# Connector.net
KiCad netlist of a schematic drawn in Altium Designer
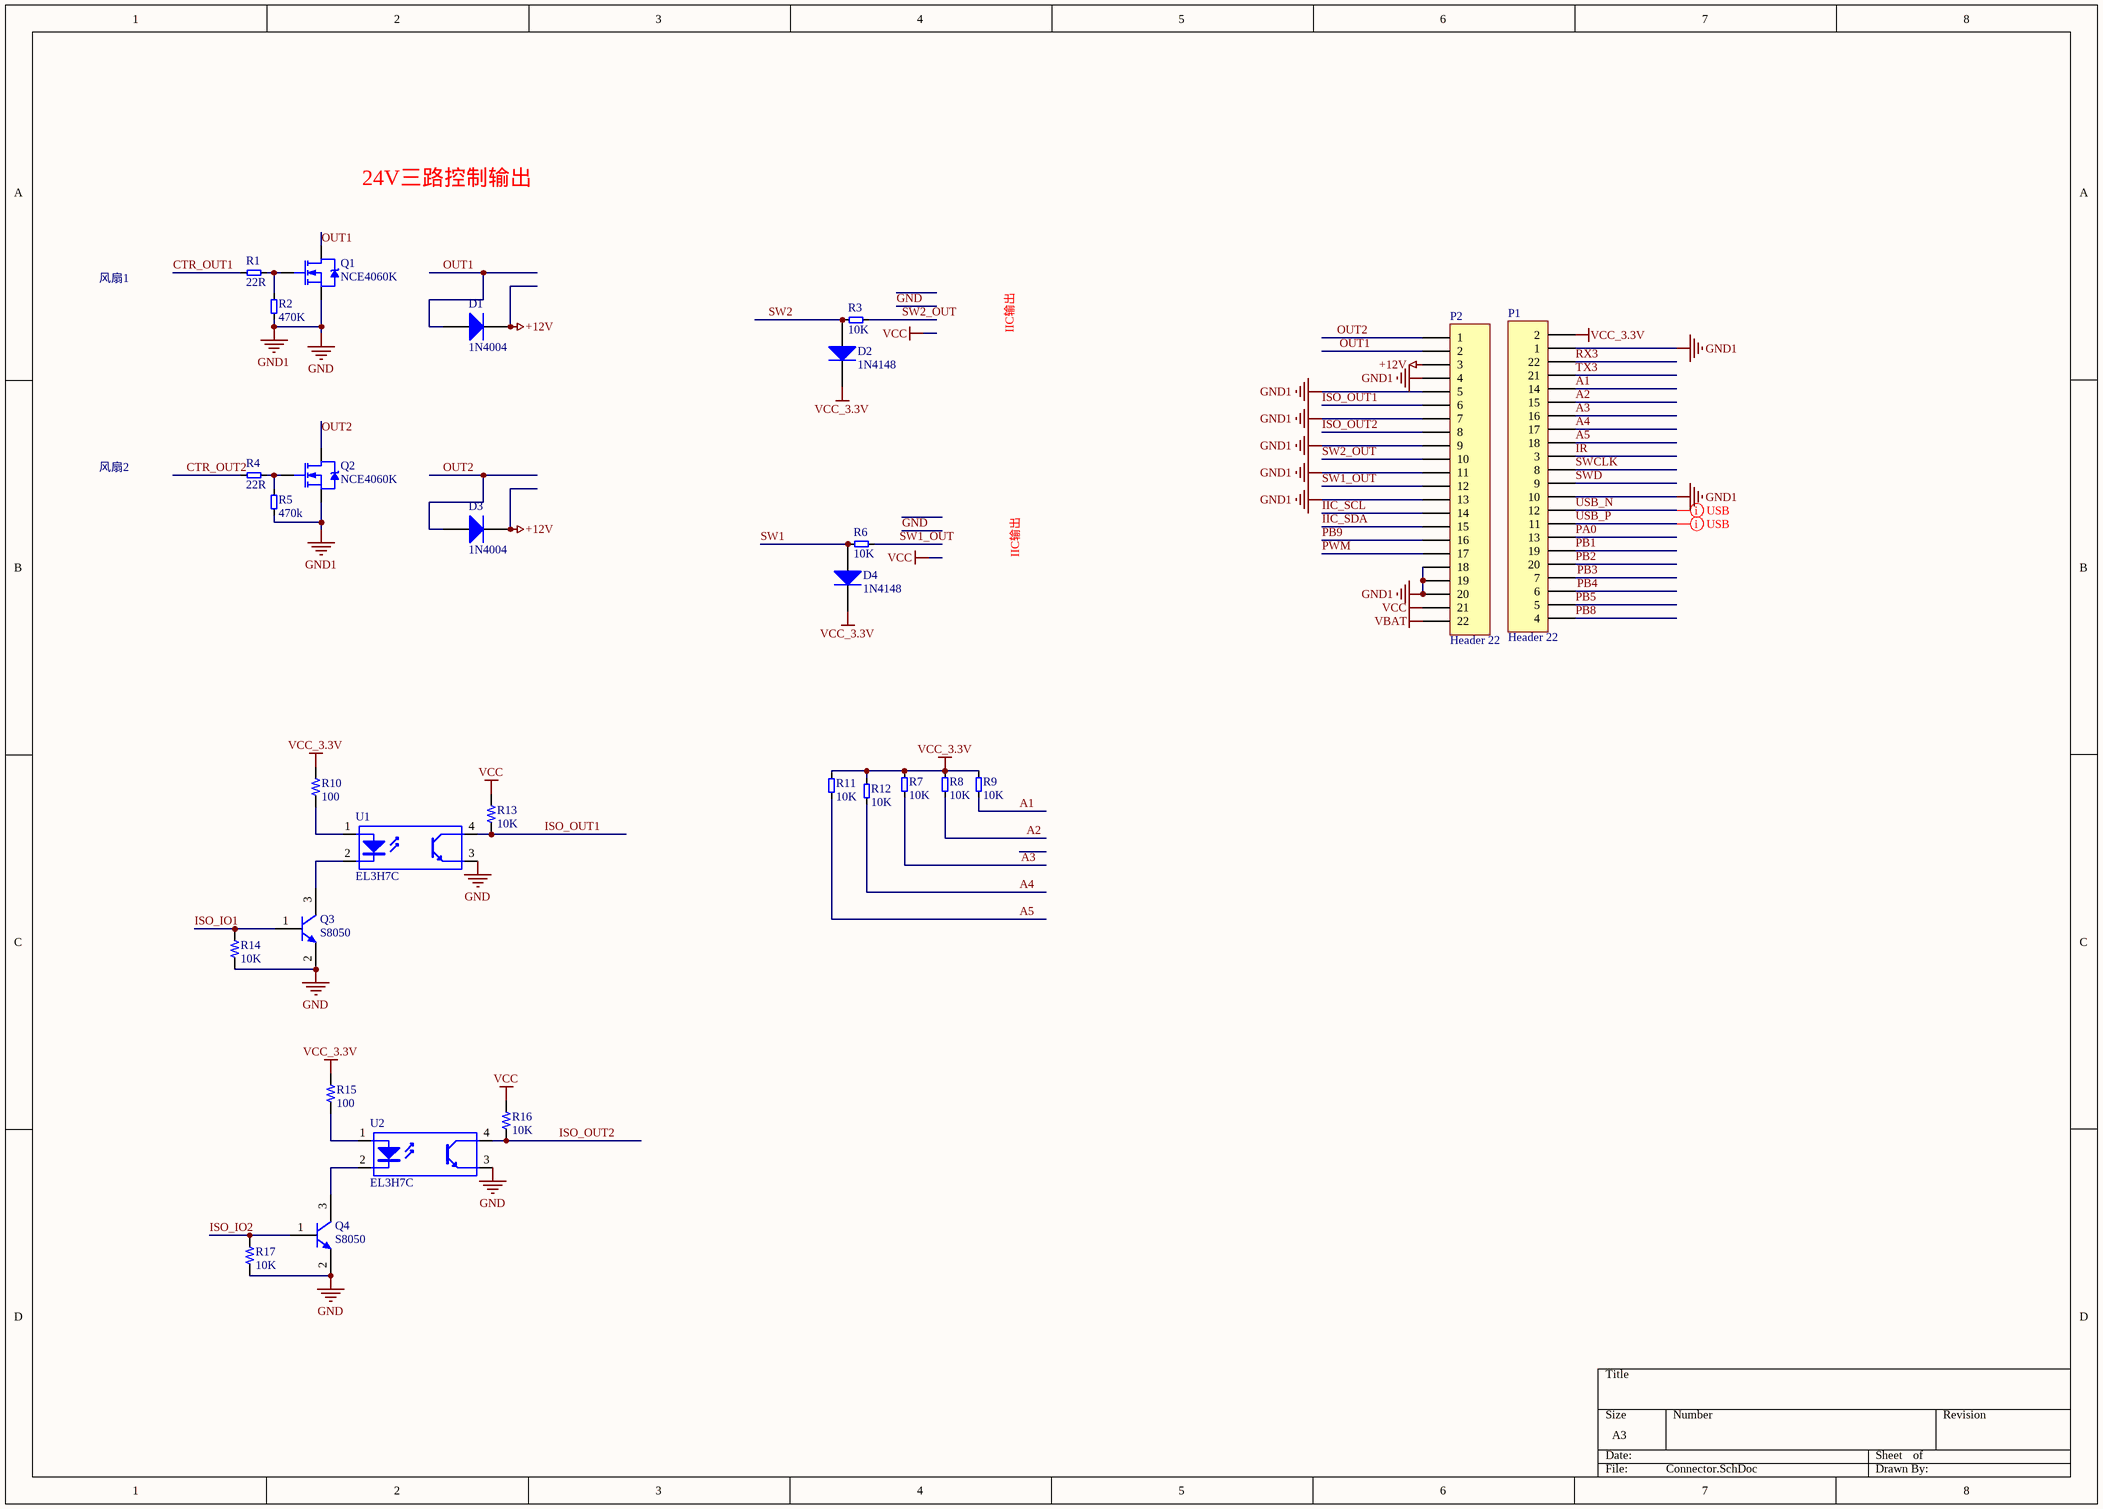
[diagram p0: Connector.SchDoc]

(export (version "E")
  (design (tool "Eeschema 10.0.6"))
  (components
    (comp (ref "D1")
      (value "1N4004")
      (footprint "SMA")
      (description "Default Diode")
      (fields (field (name "PUBLISHER") "Altium Limited"))
      (libsource (lib "SM") (part "Diode_2"))
    )
    (comp (ref "D2")
      (value "1N4148")
      (footprint "sod323")
      (description "Default Diode")
      (fields (field (name "PUBLISHER") "Altium Limited"))
      (libsource (lib "Miscellaneous Devices") (part "Diode"))
    )
    (comp (ref "D3")
      (value "1N4004")
      (footprint "SMA")
      (description "Default Diode")
      (fields (field (name "PUBLISHER") "Altium Limited"))
      (libsource (lib "SM") (part "Diode_2"))
    )
    (comp (ref "D4")
      (value "1N4148")
      (footprint "sod323")
      (description "Default Diode")
      (fields (field (name "PUBLISHER") "Altium Limited"))
      (libsource (lib "Miscellaneous Devices") (part "Diode"))
    )
    (comp (ref "P1")
      (value "Header 22")
      (footprint "pcb_module_a")
      (description "Header, 22-Pin")
      (fields (field (name "PUBLISHER") "Altium Limited"))
      (libsource (lib "") (part "Header 22_1"))
    )
    (comp (ref "P2")
      (value "Header 22")
      (footprint "pcb_module_a")
      (description "Header, 22-Pin")
      (fields (field (name "PUBLISHER") "Altium Limited"))
      (libsource (lib "Miscellaneous Connectors") (part "Header 22"))
    )
    (comp (ref "Q1")
      (value "NCE4060K")
      (footprint "TO-252-3S")
      (description "NMOSFET")
      (libsource (lib "SM") (part "NCE4060K"))
    )
    (comp (ref "Q2")
      (value "NCE4060K")
      (footprint "TO-252-3S")
      (description "NMOSFET")
      (libsource (lib "SM") (part "NCE4060K"))
    )
    (comp (ref "Q3") (value "S8050") (footprint "SOT23-3") (libsource (lib "Schlib1") (part "NPN")))
    (comp (ref "Q4") (value "S8050") (footprint "SOT23-3") (libsource (lib "Schlib1") (part "NPN")))
    (comp (ref "R1")
      (value "22R")
      (footprint "0402R")
      (description "CR85-102J")
      (libsource (lib "SMD电阻") (part "1K"))
    )
    (comp (ref "R2")
      (value "470K")
      (footprint "0402R")
      (description "CR85-102J")
      (libsource (lib "SMD电阻") (part "1K"))
    )
    (comp (ref "R3")
      (value "10K")
      (footprint "0402R")
      (description "CR85-102J")
      (libsource (lib "SMD电阻") (part "1K"))
    )
    (comp (ref "R4")
      (value "22R")
      (footprint "0402R")
      (description "CR85-102J")
      (libsource (lib "SMD电阻") (part "1K"))
    )
    (comp (ref "R5")
      (value "470k")
      (footprint "0402R")
      (description "CR85-102J")
      (libsource (lib "SMD电阻") (part "1K"))
    )
    (comp (ref "R6")
      (value "10K")
      (footprint "0402R")
      (description "CR85-102J")
      (libsource (lib "SMD电阻") (part "1K"))
    )
    (comp (ref "R7")
      (value "10K")
      (footprint "0402R")
      (description "CR85-102J")
      (libsource (lib "SMD电阻") (part "1K"))
    )
    (comp (ref "R8")
      (value "10K")
      (footprint "0402R")
      (description "CR85-102J")
      (libsource (lib "SMD电阻") (part "1K"))
    )
    (comp (ref "R9")
      (value "10K")
      (footprint "0402R")
      (description "CR85-102J")
      (libsource (lib "SMD电阻") (part "1K"))
    )
    (comp (ref "R10")
      (value "100")
      (footprint "0402R")
      (description "R")
      (libsource (lib "JRJ_1") (part "R"))
    )
    (comp (ref "R11")
      (value "10K")
      (footprint "0402R")
      (description "CR85-102J")
      (libsource (lib "SMD电阻") (part "1K"))
    )
    (comp (ref "R12")
      (value "10K")
      (footprint "0402R")
      (description "CR85-102J")
      (libsource (lib "SMD电阻") (part "1K"))
    )
    (comp (ref "R13")
      (value "10K")
      (footprint "0402R")
      (description "R")
      (libsource (lib "JRJ_1") (part "R"))
    )
    (comp (ref "R14")
      (value "10K")
      (footprint "0402R")
      (description "R")
      (libsource (lib "JRJ_1") (part "R"))
    )
    (comp (ref "R15")
      (value "100")
      (footprint "0402R")
      (description "R")
      (libsource (lib "JRJ_1") (part "R"))
    )
    (comp (ref "R16")
      (value "10K")
      (footprint "0402R")
      (description "R")
      (libsource (lib "JRJ_1") (part "R"))
    )
    (comp (ref "R17")
      (value "10K")
      (footprint "0402R")
      (description "R")
      (libsource (lib "JRJ_1") (part "R"))
    )
    (comp (ref "U1")
      (value "EL3H7C")
      (footprint "EL3H7C")
      (description "4-Pin Phototransistor Optocoupler")
      (fields (field (name "PUBLISHER") "Altium Limited"))
      (libsource (lib "Miscellaneous Devices") (part "Optoisolator1"))
    )
    (comp (ref "U2")
      (value "EL3H7C")
      (footprint "EL3H7C")
      (description "4-Pin Phototransistor Optocoupler")
      (fields (field (name "PUBLISHER") "Altium Limited"))
      (libsource (lib "Miscellaneous Devices") (part "Optoisolator1"))
    )
  )
  (nets
    (net (code "1") (name "+12V") (class "Default")
      (node (ref "D1") (pin "2") (pinfunction "K_2") (pintype "passive"))
      (node (ref "D3") (pin "2") (pinfunction "K_2") (pintype "passive"))
      (node (ref "P2") (pin "3") (pinfunction "3_3") (pintype "passive"))
    )
    (net (code "2") (name "/A1") (class "Default")
      (node (ref "P1") (pin "14") (pinfunction "14_14") (pintype "passive"))
      (node (ref "R9") (pin "1") (pinfunction "1_1") (pintype "passive"))
    )
    (net (code "3") (name "/A2") (class "Default")
      (node (ref "P1") (pin "15") (pinfunction "15_15") (pintype "passive"))
      (node (ref "R8") (pin "1") (pinfunction "1_1") (pintype "passive"))
    )
    (net (code "4") (name "/A3") (class "Default")
      (node (ref "P1") (pin "16") (pinfunction "16_16") (pintype "passive"))
      (node (ref "R7") (pin "1") (pinfunction "1_1") (pintype "passive"))
    )
    (net (code "5") (name "/A4") (class "Default")
      (node (ref "P1") (pin "17") (pinfunction "17_17") (pintype "passive"))
      (node (ref "R12") (pin "2") (pinfunction "2_2") (pintype "passive"))
    )
    (net (code "6") (name "/A5") (class "Default")
      (node (ref "P1") (pin "18") (pinfunction "18_18") (pintype "passive"))
      (node (ref "R11") (pin "1") (pinfunction "1_1") (pintype "passive"))
    )
    (net (code "7") (name "/CTR_OUT1") (class "Default")
      (node (ref "R1") (pin "1") (pinfunction "1_1") (pintype "passive"))
    )
    (net (code "8") (name "/CTR_OUT2") (class "Default")
      (node (ref "R4") (pin "1") (pinfunction "1_1") (pintype "passive"))
    )
    (net (code "9") (name "/IIC_SCL") (class "Default")
      (node (ref "P2") (pin "14") (pinfunction "14_14") (pintype "passive"))
    )
    (net (code "10") (name "/IIC_SDA") (class "Default")
      (node (ref "P2") (pin "15") (pinfunction "15_15") (pintype "passive"))
    )
    (net (code "11") (name "/IR") (class "Default")
      (node (ref "P1") (pin "3") (pinfunction "3_3") (pintype "passive"))
    )
    (net (code "12") (name "/ISO_IO1") (class "Default")
      (node (ref "Q3") (pin "1") (pinfunction "B_1") (pintype "passive"))
      (node (ref "R14") (pin "2") (pintype "passive"))
    )
    (net (code "13") (name "/ISO_IO2") (class "Default")
      (node (ref "Q4") (pin "1") (pinfunction "B_1") (pintype "passive"))
      (node (ref "R17") (pin "2") (pintype "passive"))
    )
    (net (code "14") (name "/ISO_OUT1") (class "Default")
      (node (ref "P2") (pin "6") (pinfunction "6_6") (pintype "passive"))
      (node (ref "R13") (pin "1") (pintype "passive"))
      (node (ref "U1") (pin "4") (pinfunction "C_4") (pintype "passive"))
    )
    (net (code "15") (name "/ISO_OUT2") (class "Default")
      (node (ref "P2") (pin "8") (pinfunction "8_8") (pintype "passive"))
      (node (ref "R16") (pin "1") (pintype "passive"))
      (node (ref "U2") (pin "4") (pinfunction "C_4") (pintype "passive"))
    )
    (net (code "16") (name "/OUT1") (class "Default")
      (node (ref "D1") (pin "1") (pinfunction "A_1") (pintype "passive"))
      (node (ref "P2") (pin "2") (pinfunction "2_2") (pintype "passive"))
      (node (ref "Q1") (pin "2") (pinfunction "D_2") (pintype "passive"))
    )
    (net (code "17") (name "/OUT2") (class "Default")
      (node (ref "D3") (pin "1") (pinfunction "A_1") (pintype "passive"))
      (node (ref "P2") (pin "1") (pinfunction "1_1") (pintype "passive"))
      (node (ref "Q2") (pin "2") (pinfunction "D_2") (pintype "passive"))
    )
    (net (code "18") (name "/PA0") (class "Default")
      (node (ref "P1") (pin "13") (pinfunction "13_13") (pintype "passive"))
    )
    (net (code "19") (name "/PB1") (class "Default")
      (node (ref "P1") (pin "19") (pinfunction "19_19") (pintype "passive"))
    )
    (net (code "20") (name "/PB2") (class "Default")
      (node (ref "P1") (pin "20") (pinfunction "20_20") (pintype "passive"))
    )
    (net (code "21") (name "/PB3") (class "Default")
      (node (ref "P1") (pin "7") (pinfunction "7_7") (pintype "passive"))
    )
    (net (code "22") (name "/PB4") (class "Default")
      (node (ref "P1") (pin "6") (pinfunction "6_6") (pintype "passive"))
    )
    (net (code "23") (name "/PB5") (class "Default")
      (node (ref "P1") (pin "5") (pinfunction "5_5") (pintype "passive"))
    )
    (net (code "24") (name "/PB8") (class "Default")
      (node (ref "P1") (pin "4") (pinfunction "4_4") (pintype "passive"))
    )
    (net (code "25") (name "/PB9") (class "Default")
      (node (ref "P2") (pin "16") (pinfunction "16_16") (pintype "passive"))
    )
    (net (code "26") (name "/PWM") (class "Default")
      (node (ref "P2") (pin "17") (pinfunction "17_17") (pintype "passive"))
    )
    (net (code "27") (name "/RX3") (class "Default")
      (node (ref "P1") (pin "22") (pinfunction "22_22") (pintype "passive"))
    )
    (net (code "28") (name "/SW1") (class "Default")
      (node (ref "D4") (pin "A") (pinfunction "A_A") (pintype "passive"))
      (node (ref "R6") (pin "2") (pinfunction "2_2") (pintype "passive"))
    )
    (net (code "29") (name "/SW1_OUT") (class "Default")
      (node (ref "P2") (pin "12") (pinfunction "12_12") (pintype "passive"))
      (node (ref "R6") (pin "1") (pinfunction "1_1") (pintype "passive"))
    )
    (net (code "30") (name "/SW2") (class "Default")
      (node (ref "D2") (pin "A") (pinfunction "A_A") (pintype "passive"))
      (node (ref "R3") (pin "2") (pinfunction "2_2") (pintype "passive"))
    )
    (net (code "31") (name "/SW2_OUT") (class "Default")
      (node (ref "P2") (pin "10") (pinfunction "10_10") (pintype "passive"))
      (node (ref "R3") (pin "1") (pinfunction "1_1") (pintype "passive"))
    )
    (net (code "32") (name "/SWCLK") (class "Default")
      (node (ref "P1") (pin "8") (pinfunction "8_8") (pintype "passive"))
    )
    (net (code "33") (name "/SWD") (class "Default")
      (node (ref "P1") (pin "9") (pinfunction "9_9") (pintype "passive"))
    )
    (net (code "34") (name "/TX3") (class "Default")
      (node (ref "P1") (pin "21") (pinfunction "21_21") (pintype "passive"))
    )
    (net (code "35") (name "/USB_N") (class "Default")
      (node (ref "P1") (pin "12") (pinfunction "12_12") (pintype "passive"))
    )
    (net (code "36") (name "/USB_P") (class "Default")
      (node (ref "P1") (pin "11") (pinfunction "11_11") (pintype "passive"))
    )
    (net (code "37") (name "GND") (class "Default")
      (node (ref "P1") (pin "1") (pinfunction "1_1") (pintype "passive"))
      (node (ref "P1") (pin "10") (pinfunction "10_10") (pintype "passive"))
      (node (ref "P2") (pin "11") (pinfunction "11_11") (pintype "passive"))
      (node (ref "P2") (pin "13") (pinfunction "13_13") (pintype "passive"))
      (node (ref "P2") (pin "18") (pinfunction "18_18") (pintype "passive"))
      (node (ref "P2") (pin "19") (pinfunction "19_19") (pintype "passive"))
      (node (ref "P2") (pin "20") (pinfunction "20_20") (pintype "passive"))
      (node (ref "P2") (pin "4") (pinfunction "4_4") (pintype "passive"))
      (node (ref "P2") (pin "5") (pinfunction "5_5") (pintype "passive"))
      (node (ref "P2") (pin "7") (pinfunction "7_7") (pintype "passive"))
      (node (ref "P2") (pin "9") (pinfunction "9_9") (pintype "passive"))
      (node (ref "Q1") (pin "3") (pinfunction "S_3") (pintype "passive"))
      (node (ref "Q2") (pin "3") (pinfunction "S_3") (pintype "passive"))
      (node (ref "Q3") (pin "2") (pinfunction "E_2") (pintype "passive"))
      (node (ref "Q4") (pin "2") (pinfunction "E_2") (pintype "passive"))
      (node (ref "R14") (pin "1") (pintype "passive"))
      (node (ref "R17") (pin "1") (pintype "passive"))
      (node (ref "R2") (pin "1") (pinfunction "1_1") (pintype "passive"))
      (node (ref "R5") (pin "1") (pinfunction "1_1") (pintype "passive"))
      (node (ref "U1") (pin "3") (pinfunction "E_3") (pintype "passive"))
      (node (ref "U2") (pin "3") (pinfunction "E_3") (pintype "passive"))
    )
    (net (code "38") (name "Net-(Q1-G)") (class "Default")
      (node (ref "Q1") (pin "1") (pinfunction "G_1") (pintype "passive"))
      (node (ref "R1") (pin "2") (pinfunction "2_2") (pintype "passive"))
      (node (ref "R2") (pin "2") (pinfunction "2_2") (pintype "passive"))
    )
    (net (code "39") (name "Net-(Q2-G)") (class "Default")
      (node (ref "Q2") (pin "1") (pinfunction "G_1") (pintype "passive"))
      (node (ref "R4") (pin "2") (pinfunction "2_2") (pintype "passive"))
      (node (ref "R5") (pin "2") (pinfunction "2_2") (pintype "passive"))
    )
    (net (code "40") (name "Net-(Q3-C)") (class "Default")
      (node (ref "Q3") (pin "3") (pinfunction "C_3") (pintype "passive"))
      (node (ref "U1") (pin "2") (pinfunction "K_2") (pintype "passive"))
    )
    (net (code "41") (name "Net-(Q4-C)") (class "Default")
      (node (ref "Q4") (pin "3") (pinfunction "C_3") (pintype "passive"))
      (node (ref "U2") (pin "2") (pinfunction "K_2") (pintype "passive"))
    )
    (net (code "42") (name "Net-(U1-A)") (class "Default")
      (node (ref "R10") (pin "1") (pintype "passive"))
      (node (ref "U1") (pin "1") (pinfunction "A_1") (pintype "passive"))
    )
    (net (code "43") (name "Net-(U2-A)") (class "Default")
      (node (ref "R15") (pin "1") (pintype "passive"))
      (node (ref "U2") (pin "1") (pinfunction "A_1") (pintype "passive"))
    )
    (net (code "44") (name "VBAT") (class "Default")
      (node (ref "P2") (pin "22") (pinfunction "22_22") (pintype "passive"))
    )
    (net (code "45") (name "VCC") (class "Default")
      (node (ref "P2") (pin "21") (pinfunction "21_21") (pintype "passive"))
      (node (ref "R13") (pin "2") (pintype "passive"))
      (node (ref "R16") (pin "2") (pintype "passive"))
    )
    (net (code "46") (name "VCC_3.3V") (class "Default")
      (node (ref "D2") (pin "K") (pinfunction "K_K") (pintype "passive"))
      (node (ref "D4") (pin "K") (pinfunction "K_K") (pintype "passive"))
      (node (ref "P1") (pin "2") (pinfunction "2_2") (pintype "passive"))
      (node (ref "R10") (pin "2") (pintype "passive"))
      (node (ref "R11") (pin "2") (pinfunction "2_2") (pintype "passive"))
      (node (ref "R12") (pin "1") (pinfunction "1_1") (pintype "passive"))
      (node (ref "R15") (pin "2") (pintype "passive"))
      (node (ref "R7") (pin "2") (pinfunction "2_2") (pintype "passive"))
      (node (ref "R8") (pin "2") (pinfunction "2_2") (pintype "passive"))
      (node (ref "R9") (pin "2") (pinfunction "2_2") (pintype "passive"))
    )
  )
)
